# MCU.net
KiCad netlist of a schematic drawn in Altium Designer
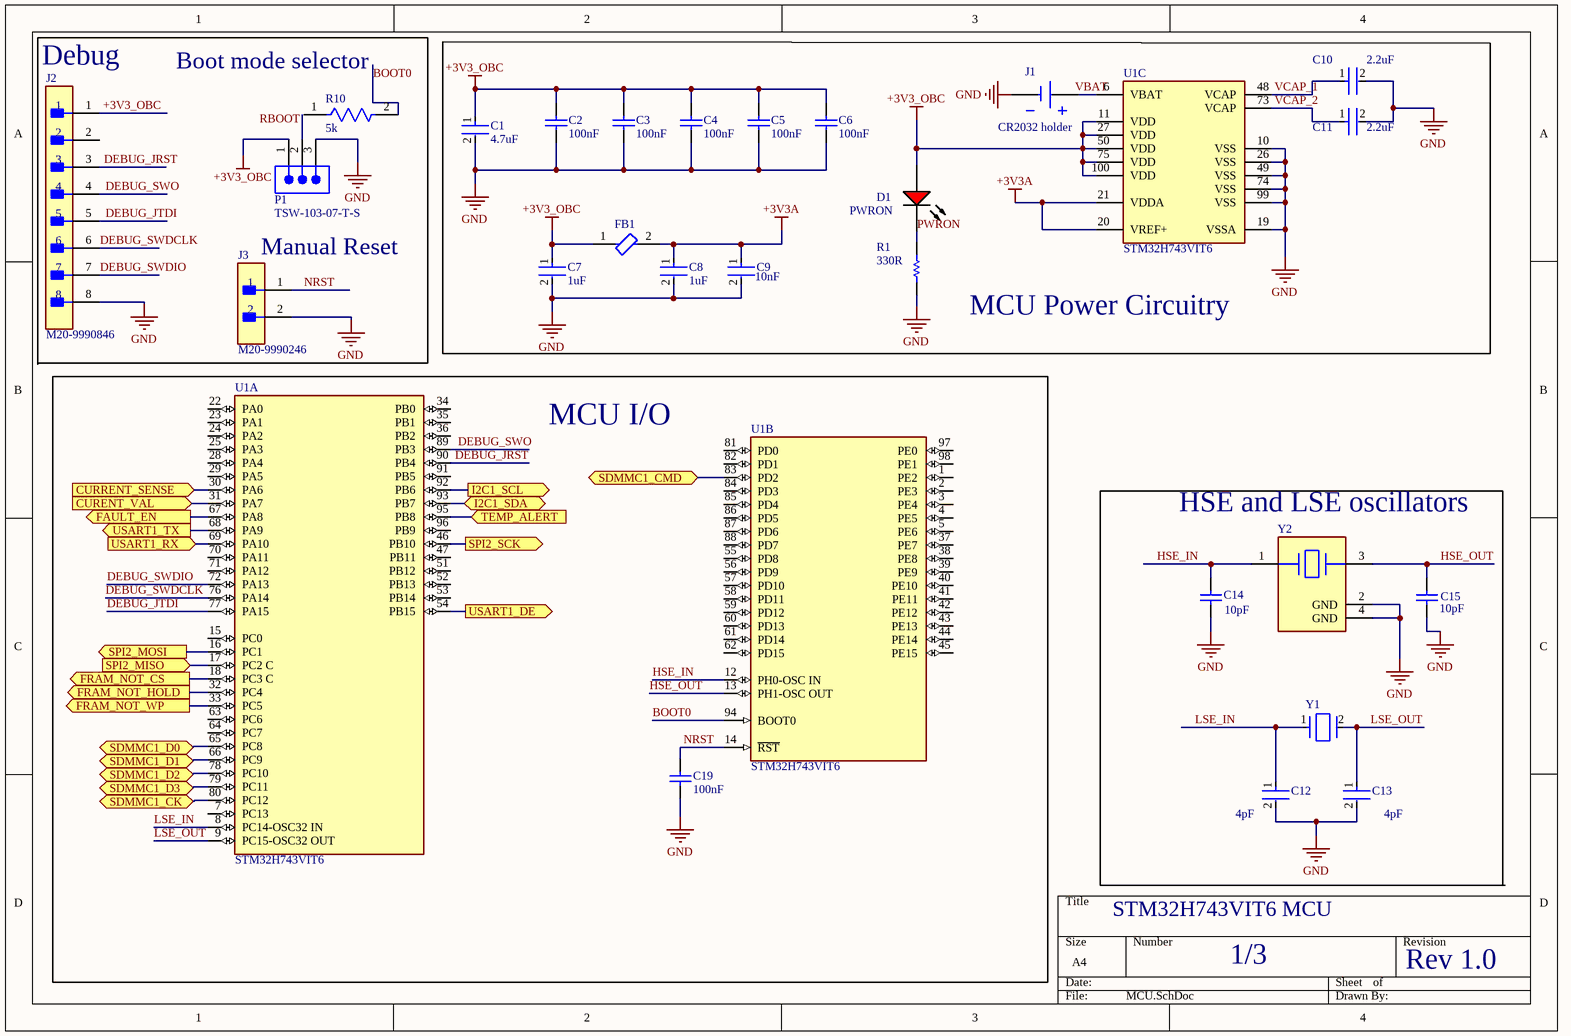
[diagram p0: MCU.SchDoc]

(export (version "E")
  (design (tool "Eeschema 10.0.6"))
  (components
    (comp (ref "C1")
      (value "4.7uF")
      (footprint "FP-0805-L_2_0_0_1-W_1_25-IPC_B")
      (description "Multilayer Ceramic Capacitor 4.7 uF 16V X7R 10% SMD 0805 T/R")
      (fields (field (name "TOLERANCE") "10%"))
      (libsource (lib "Altium Content Vault") (part "b4654b650e69147ec39a6b967a45e02"))
    )
    (comp (ref "C2")
      (value "100nF")
      (footprint "SAMS-C0603-2_M")
      (description "Multi-layer Ceramic Capacitor, -55 to 125 degC, 2-Pin SMD (0603), RoHS, Tape and Reel")
      (fields (field (name "MANUFACTURER") "Samsung Electro-Mechanics"))
      (libsource (lib "Altium Content Vault") (part "CAP-NP-2"))
    )
    (comp (ref "C3")
      (value "100nF")
      (footprint "SAMS-C0603-2_M")
      (description "Multi-layer Ceramic Capacitor, -55 to 125 degC, 2-Pin SMD (0603), RoHS, Tape and Reel")
      (fields (field (name "MANUFACTURER") "Samsung Electro-Mechanics"))
      (libsource (lib "Altium Content Vault") (part "CAP-NP-2"))
    )
    (comp (ref "C4")
      (value "100nF")
      (footprint "SAMS-C0603-2_M")
      (description "Multi-layer Ceramic Capacitor, -55 to 125 degC, 2-Pin SMD (0603), RoHS, Tape and Reel")
      (fields (field (name "MANUFACTURER") "Samsung Electro-Mechanics"))
      (libsource (lib "Altium Content Vault") (part "CAP-NP-2"))
    )
    (comp (ref "C5")
      (value "100nF")
      (footprint "SAMS-C0603-2_M")
      (description "Multi-layer Ceramic Capacitor, -55 to 125 degC, 2-Pin SMD (0603), RoHS, Tape and Reel")
      (fields (field (name "MANUFACTURER") "Samsung Electro-Mechanics"))
      (libsource (lib "Altium Content Vault") (part "CAP-NP-2"))
    )
    (comp (ref "C6")
      (value "100nF")
      (footprint "SAMS-C0603-2_M")
      (description "Multi-layer Ceramic Capacitor, -55 to 125 degC, 2-Pin SMD (0603), RoHS, Tape and Reel")
      (fields (field (name "MANUFACTURER") "Samsung Electro-Mechanics"))
      (libsource (lib "Altium Content Vault") (part "CAP-NP-2"))
    )
    (comp (ref "C7")
      (value "1uF")
      (footprint "FP-CL10-IPC_C")
      (description "Cap Ceramic 1uF 25V X5R ±10% Pad SMD 0603 +85°C T/R")
      (fields (field (name "VOLTAGE") "25V") (field (name "TOLERANCE") "10%"))
      (libsource (lib "Altium Content Vault") (part "b4654b650e69147ec39a6b967a45e02"))
    )
    (comp (ref "C8")
      (value "1uF")
      (footprint "FP-CL10-IPC_C")
      (description "Cap Ceramic 1uF 25V X5R ±10% Pad SMD 0603 +85°C T/R")
      (fields (field (name "VOLTAGE") "25V") (field (name "TOLERANCE") "10%"))
      (libsource (lib "Altium Content Vault") (part "b4654b650e69147ec39a6b967a45e02"))
    )
    (comp (ref "C9")
      (value "10nF")
      (footprint "FP-CC0402-MFG")
      (description "CAP CER 10000PF 10V X7R 0402")
      (fields
        (field (name "MANUFACTURER") "YAGEO")
        (field (name "MANUFACTURER PART NUMBER") "CC0402KRX7R6BB103")
      )
      (libsource (lib "Altium Content Vault") (part "11868f565c42a9108669ba33697ecf6"))
    )
    (comp (ref "C10")
      (value "2.2uF")
      (footprint "FP-CC0805-0_85-MFG")
      (description "CAP CER 2.2UF 25V X7R 0805")
      (fields
        (field (name "MANUFACTURER PART NUMBER") "CC0805KKX7R8BB225")
        (field (name "OCTOPART") "https://octopart.com/cc0805kkx7r8bb225-yageo-42522865")
      )
      (libsource (lib "Altium Content Vault") (part "11868f565c42a9108669ba33697ecf6"))
    )
    (comp (ref "C11")
      (value "2.2uF")
      (footprint "FP-CC0805-0_85-MFG")
      (description "CAP CER 2.2UF 25V X7R 0805")
      (fields
        (field (name "MANUFACTURER PART NUMBER") "CC0805KKX7R8BB225")
        (field (name "OCTOPART") "https://octopart.com/cc0805kkx7r8bb225-yageo-42522865")
      )
      (libsource (lib "Altium Content Vault") (part "11868f565c42a9108669ba33697ecf6"))
    )
    (comp (ref "C12")
      (value "4pF")
      (footprint "FP-GRM033-0_03-IPC_B")
      (description "Chip Multilayer Ceramic Capacitors for General Purpose, 0201, 4.0pF, C0G, 30ppm/°C, 0.25pF, 25V")
      (libsource (lib "Altium Content Vault") (part "b4654b650e69147ec39a6b967a45e02"))
    )
    (comp (ref "C13")
      (value "4pF")
      (footprint "FP-GRM033-0_03-IPC_B")
      (description "Chip Multilayer Ceramic Capacitors for General Purpose, 0201, 4.0pF, C0G, 30ppm/°C, 0.25pF, 25V")
      (libsource (lib "Altium Content Vault") (part "b4654b650e69147ec39a6b967a45e02"))
    )
    (comp (ref "C14")
      (value "10pF")
      (footprint "CAPC1005X55X25ML05T05")
      (description "Chip Capacitor, 10 pF, +/- 5%, 50 V, -55 to 125 degC, 0402 (1005 Metric), RoHS, Tape and Reel")
      (fields (field (name "TOLERANCE") "5%") (field (name "MANUFACTURER") "Yageo"))
      (libsource (lib "Altium Content Vault") (part "CAP-NP-2"))
    )
    (comp (ref "C15")
      (value "10pF")
      (footprint "CAPC1005X55X25ML05T05")
      (description "Chip Capacitor, 10 pF, +/- 5%, 50 V, -55 to 125 degC, 0402 (1005 Metric), RoHS, Tape and Reel")
      (fields (field (name "TOLERANCE") "5%") (field (name "MANUFACTURER") "Yageo"))
      (libsource (lib "Altium Content Vault") (part "CAP-NP-2"))
    )
    (comp (ref "C19")
      (value "100nF")
      (footprint "SAMS-C0603-2_M")
      (description "Multi-layer Ceramic Capacitor, -55 to 125 degC, 2-Pin SMD (0603), RoHS, Tape and Reel")
      (fields (field (name "MANUFACTURER") "Samsung Electro-Mechanics"))
      (libsource (lib "Altium Content Vault") (part "CAP-NP-2"))
    )
    (comp (ref "D1")
      (value "PWRON")
      (footprint "EVRL-0603-2_V")
      (description "Chip LED, Red, 5 V, 25 mA, -40 to 85 degC, 2-Pin SMD (0603), RoHS, Tape and Reel")
      (fields (field (name "MANUFACTURER") "Everlight Electronics"))
      (libsource (lib "Altium Content Vault") (part "LED-RED-AK-2"))
    )
    (comp (ref "FB1")
      (value "MMZ1005D121CTD25")
      (footprint "FP-MMZ1005-IPC_C")
      (description "Signal Line Ferrite Bead 120Ω @ 100MHz 350mA DCR 600mΩ AEC-Q200 SMD 0402")
      (libsource (lib "Altium Content Vault") (part "5f30dd21d616792df468990f7003faa"))
    )
    (comp (ref "J1")
      (value "CR2032 holder")
      (footprint "KEYSTONE-1025-7-2_V")
      (description "Holder for 2477 or 2430 Cells P/N 1025-7, Body 27.762 x 30.963 mm, THM")
      (fields (field (name "PARTNUMBER") "1025-7") (field (name "MANUFACTURER") "Keystone"))
      (libsource (lib "Altium Content Vault") (part "KEYSTONE-1025-7-2"))
    )
    (comp (ref "J2")
      (value "M20-9990846")
      (footprint "FP-M20-9990846-MFG")
      (description "CONN HEADER VERT 8POS 2.54MM")
      (libsource (lib "Altium Content Vault") (part "99ec2b232beb5d2356d4d77f6a047f0"))
    )
    (comp (ref "J3")
      (value "M20-9990246")
      (footprint "FP-M20-9990246-MFG")
      (description "CONN HEADER VERT 2POS 2.54MM")
      (fields
        (field (name "OCTOPART") "https://octopart.com/m20-9990246-harwin-2590635")
        (field (name "MANUFACTURER") "Harwin")
      )
      (libsource (lib "Altium Content Vault") (part "3bc925449376181038e59eaffc5286c"))
    )
    (comp (ref "P1")
      (value "TSW-103-07-T-S")
      (footprint "SMTC-TSW-103-07-X-S")
      (description "0.025\" SQ Post Header, Through-hole, Vertical, -55 to 105 degC, 2.54 mm Pitch, 3-Pin, Male, RoHS")
      (fields (field (name "MANUFACTURER") "Samtec"))
      (libsource (lib "Altium Content Vault") (part "SMTC-TSW-103-X-X-S-X"))
    )
    (comp (ref "R1")
      (value "330R")
      (footprint "RESC1608X55X25NL10T15")
      (description "Chip Resistor, 330 Ohm, +/- 1%, 0.1 W, -55 to 155 degC, 0603 (1608 Metric), RoHS, Tape and Reel")
      (fields (field (name "TOLERANCE") "10%"))
      (libsource (lib "Altium Content Vault") (part "RES-2"))
    )
    (comp (ref "R10")
      (value "5k")
      (footprint "FP-MCR01-MFG")
      (description "Thick Film Chip Resistor, 0402, 5.1kΩ, 1%, 100ppm/°C, 0.063W, 50V")
      (fields (field (name "TOLERANCE") "1%"))
      (libsource (lib "Altium Content Vault") (part "1029c3af85768c4190bb7ad29bc67b5"))
    )
    (comp (ref "U1")
      (value "STM32H743VIT6")
      (footprint "FP-LQFP100-1L-MFG")
      (description "IC MCU 32BIT 2MB FLASH 100LQFP")
      (fields
        (field (name "OCTOPART") "https://octopart.com/stm32h743vit6-stmicroelectronics-76372527")
        (field (name "MANUFACTURER") "STMicroelectronics")
      )
      (libsource (lib "Altium Content Vault") (part "01082ce2885d1d16a22823c45526fe6"))
    )
    (comp (ref "Y1")
      (value "ABS06-107-32.768KHZ-T")
      (footprint "FP-ABS06-MFG")
      (description "CRYSTAL 32.7680KHZ 4PF SMD")
      (fields (field (name "TOLERANCE") "20ppm"))
      (libsource (lib "Altium Content Vault") (part "c23a69dc6c9e2f18f2079038eb95dd1"))
    )
    (comp (ref "Y2")
      (value "ABM3B-25.000MHZ-10-1-U-T")
      (footprint "FP-ABM3B-MFG")
      (description "Crystal 25MHz ±10ppm 10pF SMD-4 5mm x 3.2mm")
      (fields (field (name "TOLERANCE") "10ppm"))
      (libsource (lib "Altium Content Vault") (part "48e526d86b7f2615d98721063c72f49"))
    )
  )
  (nets
    (net (code "1") (name "+3V3A") (class "Default")
      (node (ref "C8") (pin "1") (pinfunction "1_1") (pintype "passive"))
      (node (ref "C9") (pin "1") (pinfunction "1_1") (pintype "passive"))
      (node (ref "FB1") (pin "2") (pinfunction "2_2") (pintype "passive"))
      (node (ref "U1") (pin "20") (pinfunction "VREF+_20") (pintype "power_in"))
      (node (ref "U1") (pin "21") (pinfunction "VDDA_21") (pintype "power_in"))
    )
    (net (code "2") (name "+3V3_OBC") (class "Default")
      (node (ref "C1") (pin "1") (pinfunction "1_1") (pintype "passive"))
      (node (ref "C2") (pin "2") (pinfunction "2_2") (pintype "passive"))
      (node (ref "C3") (pin "2") (pinfunction "2_2") (pintype "passive"))
      (node (ref "C4") (pin "2") (pinfunction "2_2") (pintype "passive"))
      (node (ref "C5") (pin "2") (pinfunction "2_2") (pintype "passive"))
      (node (ref "C6") (pin "2") (pinfunction "2_2") (pintype "passive"))
      (node (ref "C7") (pin "1") (pinfunction "1_1") (pintype "passive"))
      (node (ref "D1") (pin "1") (pinfunction "A_1") (pintype "passive"))
      (node (ref "FB1") (pin "1") (pinfunction "1_1") (pintype "passive"))
      (node (ref "J2") (pin "1") (pinfunction "1_1") (pintype "passive"))
      (node (ref "P1") (pin "1") (pinfunction "1_1") (pintype "passive"))
      (node (ref "U1") (pin "100") (pinfunction "VDD_100") (pintype "power_in"))
      (node (ref "U1") (pin "11") (pinfunction "VDD_11") (pintype "power_in"))
      (node (ref "U1") (pin "27") (pinfunction "VDD_27") (pintype "power_in"))
      (node (ref "U1") (pin "50") (pinfunction "VDD_50") (pintype "power_in"))
      (node (ref "U1") (pin "75") (pinfunction "VDD_75") (pintype "power_in"))
    )
    (net (code "3") (name "/BOOT0") (class "Default")
      (node (ref "R10") (pin "2") (pinfunction "2_2") (pintype "passive"))
      (node (ref "U1") (pin "94") (pinfunction "BOOT0_94") (pintype "input"))
    )
    (net (code "4") (name "/CURENT_VAL") (class "Default")
      (node (ref "U1") (pin "31") (pinfunction "PA7_31") (pintype "bidirectional"))
    )
    (net (code "5") (name "/CURRENT_SENSE") (class "Default")
      (node (ref "U1") (pin "30") (pinfunction "PA6_30") (pintype "bidirectional"))
    )
    (net (code "6") (name "/DEBUG_JRST") (class "Default")
      (node (ref "J2") (pin "3") (pinfunction "3_3") (pintype "passive"))
      (node (ref "U1") (pin "90") (pinfunction "PB4_90") (pintype "bidirectional"))
    )
    (net (code "7") (name "/DEBUG_JTDI") (class "Default")
      (node (ref "J2") (pin "5") (pinfunction "5_5") (pintype "passive"))
      (node (ref "U1") (pin "77") (pinfunction "PA15_77") (pintype "bidirectional"))
    )
    (net (code "8") (name "/DEBUG_SWDCLK") (class "Default")
      (node (ref "J2") (pin "6") (pinfunction "6_6") (pintype "passive"))
      (node (ref "U1") (pin "76") (pinfunction "PA14_76") (pintype "bidirectional"))
    )
    (net (code "9") (name "/DEBUG_SWDIO") (class "Default")
      (node (ref "J2") (pin "7") (pinfunction "7_7") (pintype "passive"))
      (node (ref "U1") (pin "72") (pinfunction "PA13_72") (pintype "bidirectional"))
    )
    (net (code "10") (name "/DEBUG_SWO") (class "Default")
      (node (ref "J2") (pin "4") (pinfunction "4_4") (pintype "passive"))
      (node (ref "U1") (pin "89") (pinfunction "PB3_89") (pintype "bidirectional"))
    )
    (net (code "11") (name "/FAULT_EN") (class "Default")
      (node (ref "U1") (pin "67") (pinfunction "PA8_67") (pintype "bidirectional"))
    )
    (net (code "12") (name "/FRAM_NOT_CS") (class "Default")
      (node (ref "U1") (pin "18") (pinfunction "PC3_C_18") (pintype "bidirectional"))
    )
    (net (code "13") (name "/FRAM_NOT_HOLD") (class "Default")
      (node (ref "U1") (pin "32") (pinfunction "PC4_32") (pintype "bidirectional"))
    )
    (net (code "14") (name "/FRAM_NOT_WP") (class "Default")
      (node (ref "U1") (pin "33") (pinfunction "PC5_33") (pintype "bidirectional"))
    )
    (net (code "15") (name "/HSE_IN") (class "Default")
      (node (ref "C14") (pin "2") (pinfunction "2_2") (pintype "passive"))
      (node (ref "U1") (pin "12") (pinfunction "PH0-OSC_IN_12") (pintype "bidirectional"))
      (node (ref "Y2") (pin "1") (pinfunction "1_1") (pintype "passive"))
    )
    (net (code "16") (name "/HSE_OUT") (class "Default")
      (node (ref "C15") (pin "2") (pinfunction "2_2") (pintype "passive"))
      (node (ref "U1") (pin "13") (pinfunction "PH1-OSC_OUT_13") (pintype "bidirectional"))
      (node (ref "Y2") (pin "3") (pinfunction "3_3") (pintype "passive"))
    )
    (net (code "17") (name "/I2C1_SCL") (class "Default")
      (node (ref "U1") (pin "92") (pinfunction "PB6_92") (pintype "bidirectional"))
    )
    (net (code "18") (name "/I2C1_SDA") (class "Default")
      (node (ref "U1") (pin "93") (pinfunction "PB7_93") (pintype "bidirectional"))
    )
    (net (code "19") (name "/LSE_IN") (class "Default")
      (node (ref "C12") (pin "1") (pinfunction "1_1") (pintype "passive"))
      (node (ref "U1") (pin "8") (pinfunction "PC14-OSC32_IN_8") (pintype "bidirectional"))
      (node (ref "Y1") (pin "1") (pinfunction "1_1") (pintype "passive"))
    )
    (net (code "20") (name "/LSE_OUT") (class "Default")
      (node (ref "C13") (pin "1") (pinfunction "1_1") (pintype "passive"))
      (node (ref "U1") (pin "9") (pinfunction "PC15-OSC32_OUT_9") (pintype "bidirectional"))
      (node (ref "Y1") (pin "2") (pinfunction "2_2") (pintype "passive"))
    )
    (net (code "21") (name "/NRST") (class "Default")
      (node (ref "C19") (pin "2") (pinfunction "2_2") (pintype "passive"))
      (node (ref "J3") (pin "1") (pinfunction "1_1") (pintype "passive"))
      (node (ref "U1") (pin "14") (pinfunction "~{RST}_14") (pintype "input"))
    )
    (net (code "22") (name "/PWRON") (class "Default")
      (node (ref "D1") (pin "2") (pinfunction "K_2") (pintype "passive"))
      (node (ref "R1") (pin "2") (pinfunction "2_2") (pintype "passive"))
    )
    (net (code "24") (name "/SDMMC1_CK") (class "Default")
      (node (ref "U1") (pin "80") (pinfunction "PC12_80") (pintype "bidirectional"))
    )
    (net (code "25") (name "/SDMMC1_CMD") (class "Default")
      (node (ref "U1") (pin "83") (pinfunction "PD2_83") (pintype "bidirectional"))
    )
    (net (code "26") (name "/SDMMC1_D0") (class "Default")
      (node (ref "U1") (pin "65") (pinfunction "PC8_65") (pintype "bidirectional"))
    )
    (net (code "27") (name "/SDMMC1_D1") (class "Default")
      (node (ref "U1") (pin "66") (pinfunction "PC9_66") (pintype "bidirectional"))
    )
    (net (code "28") (name "/SDMMC1_D2") (class "Default")
      (node (ref "U1") (pin "78") (pinfunction "PC10_78") (pintype "bidirectional"))
    )
    (net (code "29") (name "/SDMMC1_D3") (class "Default")
      (node (ref "U1") (pin "79") (pinfunction "PC11_79") (pintype "bidirectional"))
    )
    (net (code "30") (name "/SPI2_MISO") (class "Default")
      (node (ref "U1") (pin "17") (pinfunction "PC2_C_17") (pintype "bidirectional"))
    )
    (net (code "31") (name "/SPI2_MOSI") (class "Default")
      (node (ref "U1") (pin "16") (pinfunction "PC1_16") (pintype "bidirectional"))
    )
    (net (code "32") (name "/SPI2_SCK") (class "Default")
      (node (ref "U1") (pin "46") (pinfunction "PB10_46") (pintype "bidirectional"))
    )
    (net (code "33") (name "/TEMP_ALERT") (class "Default")
      (node (ref "U1") (pin "95") (pinfunction "PB8_95") (pintype "bidirectional"))
    )
    (net (code "34") (name "/USART1_DE") (class "Default")
      (node (ref "U1") (pin "54") (pinfunction "PB15_54") (pintype "bidirectional"))
    )
    (net (code "35") (name "/USART1_RX") (class "Default")
      (node (ref "U1") (pin "69") (pinfunction "PA10_69") (pintype "bidirectional"))
    )
    (net (code "36") (name "/USART1_TX") (class "Default")
      (node (ref "U1") (pin "68") (pinfunction "PA9_68") (pintype "bidirectional"))
    )
    (net (code "38") (name "/VCAP_1") (class "Default")
      (node (ref "C10") (pin "1") (pinfunction "1_1") (pintype "passive"))
      (node (ref "U1") (pin "48") (pinfunction "VCAP_48") (pintype "passive"))
    )
    (net (code "39") (name "/VCAP_2") (class "Default")
      (node (ref "C11") (pin "1") (pinfunction "1_1") (pintype "passive"))
      (node (ref "U1") (pin "73") (pinfunction "VCAP_73") (pintype "passive"))
    )
    (net (code "40") (name "GND") (class "Default")
      (node (ref "C1") (pin "2") (pinfunction "2_2") (pintype "passive"))
      (node (ref "C10") (pin "2") (pinfunction "2_2") (pintype "passive"))
      (node (ref "C11") (pin "2") (pinfunction "2_2") (pintype "passive"))
      (node (ref "C12") (pin "2") (pinfunction "2_2") (pintype "passive"))
      (node (ref "C13") (pin "2") (pinfunction "2_2") (pintype "passive"))
      (node (ref "C14") (pin "1") (pinfunction "1_1") (pintype "passive"))
      (node (ref "C15") (pin "1") (pinfunction "1_1") (pintype "passive"))
      (node (ref "C19") (pin "1") (pinfunction "1_1") (pintype "passive"))
      (node (ref "C2") (pin "1") (pinfunction "1_1") (pintype "passive"))
      (node (ref "C3") (pin "1") (pinfunction "1_1") (pintype "passive"))
      (node (ref "C4") (pin "1") (pinfunction "1_1") (pintype "passive"))
      (node (ref "C5") (pin "1") (pinfunction "1_1") (pintype "passive"))
      (node (ref "C6") (pin "1") (pinfunction "1_1") (pintype "passive"))
      (node (ref "C7") (pin "2") (pinfunction "2_2") (pintype "passive"))
      (node (ref "C8") (pin "2") (pinfunction "2_2") (pintype "passive"))
      (node (ref "C9") (pin "2") (pinfunction "2_2") (pintype "passive"))
      (node (ref "J1") (pin "2") (pinfunction "-_2") (pintype "passive"))
      (node (ref "J2") (pin "8") (pinfunction "8_8") (pintype "passive"))
      (node (ref "J3") (pin "2") (pinfunction "2_2") (pintype "passive"))
      (node (ref "P1") (pin "3") (pinfunction "3_3") (pintype "passive"))
      (node (ref "R1") (pin "1") (pinfunction "1_1") (pintype "passive"))
      (node (ref "U1") (pin "10") (pinfunction "VSS_10") (pintype "power_in"))
      (node (ref "U1") (pin "19") (pinfunction "VSSA_19") (pintype "power_in"))
      (node (ref "U1") (pin "26") (pinfunction "VSS_26") (pintype "power_in"))
      (node (ref "U1") (pin "49") (pinfunction "VSS_49") (pintype "power_in"))
      (node (ref "U1") (pin "74") (pinfunction "VSS_74") (pintype "power_in"))
      (node (ref "U1") (pin "99") (pinfunction "VSS_99") (pintype "power_in"))
      (node (ref "Y2") (pin "2") (pinfunction "GND_2") (pintype "power_in"))
      (node (ref "Y2") (pin "4") (pinfunction "GND_4") (pintype "power_in"))
    )
    (net (code "41") (name "Net-(J1-+)") (class "Default")
      (node (ref "J1") (pin "1") (pinfunction "+_1") (pintype "passive"))
      (node (ref "U1") (pin "6") (pinfunction "VBAT_6") (pintype "power_in"))
    )
    (net (code "42") (name "unconnected-(J2-Pad2)") (class "Default")
      (node (ref "J2") (pin "2") (pinfunction "2_2") (pintype "passive"))
    )
    (net (code "43") (name "unconnected-(P1-Pad2)") (class "Default")
      (node (ref "P1") (pin "2") (pinfunction "2_2") (pintype "passive"))
    )
    (net (code "44") (name "unconnected-(R10-Pad1)") (class "Default")
      (node (ref "R10") (pin "1") (pinfunction "1_1") (pintype "passive"))
    )
    (net (code "45") (name "unconnected-(U1A-PA0-Pad22)") (class "Default")
      (node (ref "U1") (pin "22") (pinfunction "PA0_22") (pintype "bidirectional"))
    )
    (net (code "46") (name "unconnected-(U1A-PA1-Pad23)") (class "Default")
      (node (ref "U1") (pin "23") (pinfunction "PA1_23") (pintype "bidirectional"))
    )
    (net (code "47") (name "unconnected-(U1A-PA2-Pad24)") (class "Default")
      (node (ref "U1") (pin "24") (pinfunction "PA2_24") (pintype "bidirectional"))
    )
    (net (code "48") (name "unconnected-(U1A-PA3-Pad25)") (class "Default")
      (node (ref "U1") (pin "25") (pinfunction "PA3_25") (pintype "bidirectional"))
    )
    (net (code "49") (name "unconnected-(U1A-PA4-Pad28)") (class "Default")
      (node (ref "U1") (pin "28") (pinfunction "PA4_28") (pintype "bidirectional"))
    )
    (net (code "50") (name "unconnected-(U1A-PA5-Pad29)") (class "Default")
      (node (ref "U1") (pin "29") (pinfunction "PA5_29") (pintype "bidirectional"))
    )
    (net (code "51") (name "unconnected-(U1A-PA11-Pad70)") (class "Default")
      (node (ref "U1") (pin "70") (pinfunction "PA11_70") (pintype "bidirectional"))
    )
    (net (code "52") (name "unconnected-(U1A-PA12-Pad71)") (class "Default")
      (node (ref "U1") (pin "71") (pinfunction "PA12_71") (pintype "bidirectional"))
    )
    (net (code "53") (name "unconnected-(U1A-PB0-Pad34)") (class "Default")
      (node (ref "U1") (pin "34") (pinfunction "PB0_34") (pintype "bidirectional"))
    )
    (net (code "54") (name "unconnected-(U1A-PB1-Pad35)") (class "Default")
      (node (ref "U1") (pin "35") (pinfunction "PB1_35") (pintype "bidirectional"))
    )
    (net (code "55") (name "unconnected-(U1A-PB2-Pad36)") (class "Default")
      (node (ref "U1") (pin "36") (pinfunction "PB2_36") (pintype "bidirectional"))
    )
    (net (code "56") (name "unconnected-(U1A-PB5-Pad91)") (class "Default")
      (node (ref "U1") (pin "91") (pinfunction "PB5_91") (pintype "bidirectional"))
    )
    (net (code "57") (name "unconnected-(U1A-PB9-Pad96)") (class "Default")
      (node (ref "U1") (pin "96") (pinfunction "PB9_96") (pintype "bidirectional"))
    )
    (net (code "58") (name "unconnected-(U1A-PB11-Pad47)") (class "Default")
      (node (ref "U1") (pin "47") (pinfunction "PB11_47") (pintype "bidirectional"))
    )
    (net (code "59") (name "unconnected-(U1A-PB12-Pad51)") (class "Default")
      (node (ref "U1") (pin "51") (pinfunction "PB12_51") (pintype "bidirectional"))
    )
    (net (code "60") (name "unconnected-(U1A-PB13-Pad52)") (class "Default")
      (node (ref "U1") (pin "52") (pinfunction "PB13_52") (pintype "bidirectional"))
    )
    (net (code "61") (name "unconnected-(U1A-PB14-Pad53)") (class "Default")
      (node (ref "U1") (pin "53") (pinfunction "PB14_53") (pintype "bidirectional"))
    )
    (net (code "62") (name "unconnected-(U1A-PC0-Pad15)") (class "Default")
      (node (ref "U1") (pin "15") (pinfunction "PC0_15") (pintype "bidirectional"))
    )
    (net (code "63") (name "unconnected-(U1A-PC6-Pad63)") (class "Default")
      (node (ref "U1") (pin "63") (pinfunction "PC6_63") (pintype "bidirectional"))
    )
    (net (code "64") (name "unconnected-(U1A-PC7-Pad64)") (class "Default")
      (node (ref "U1") (pin "64") (pinfunction "PC7_64") (pintype "bidirectional"))
    )
    (net (code "65") (name "unconnected-(U1A-PC13-Pad7)") (class "Default")
      (node (ref "U1") (pin "7") (pinfunction "PC13_7") (pintype "bidirectional"))
    )
    (net (code "66") (name "unconnected-(U1B-PD0-Pad81)") (class "Default")
      (node (ref "U1") (pin "81") (pinfunction "PD0_81") (pintype "bidirectional"))
    )
    (net (code "67") (name "unconnected-(U1B-PD1-Pad82)") (class "Default")
      (node (ref "U1") (pin "82") (pinfunction "PD1_82") (pintype "bidirectional"))
    )
    (net (code "68") (name "unconnected-(U1B-PD3-Pad84)") (class "Default")
      (node (ref "U1") (pin "84") (pinfunction "PD3_84") (pintype "bidirectional"))
    )
    (net (code "69") (name "unconnected-(U1B-PD4-Pad85)") (class "Default")
      (node (ref "U1") (pin "85") (pinfunction "PD4_85") (pintype "bidirectional"))
    )
    (net (code "70") (name "unconnected-(U1B-PD5-Pad86)") (class "Default")
      (node (ref "U1") (pin "86") (pinfunction "PD5_86") (pintype "bidirectional"))
    )
    (net (code "71") (name "unconnected-(U1B-PD6-Pad87)") (class "Default")
      (node (ref "U1") (pin "87") (pinfunction "PD6_87") (pintype "bidirectional"))
    )
    (net (code "72") (name "unconnected-(U1B-PD7-Pad88)") (class "Default")
      (node (ref "U1") (pin "88") (pinfunction "PD7_88") (pintype "bidirectional"))
    )
    (net (code "73") (name "unconnected-(U1B-PD8-Pad55)") (class "Default")
      (node (ref "U1") (pin "55") (pinfunction "PD8_55") (pintype "bidirectional"))
    )
    (net (code "74") (name "unconnected-(U1B-PD9-Pad56)") (class "Default")
      (node (ref "U1") (pin "56") (pinfunction "PD9_56") (pintype "bidirectional"))
    )
    (net (code "75") (name "unconnected-(U1B-PD10-Pad57)") (class "Default")
      (node (ref "U1") (pin "57") (pinfunction "PD10_57") (pintype "bidirectional"))
    )
    (net (code "76") (name "unconnected-(U1B-PD11-Pad58)") (class "Default")
      (node (ref "U1") (pin "58") (pinfunction "PD11_58") (pintype "bidirectional"))
    )
    (net (code "77") (name "unconnected-(U1B-PD12-Pad59)") (class "Default")
      (node (ref "U1") (pin "59") (pinfunction "PD12_59") (pintype "bidirectional"))
    )
    (net (code "78") (name "unconnected-(U1B-PD13-Pad60)") (class "Default")
      (node (ref "U1") (pin "60") (pinfunction "PD13_60") (pintype "bidirectional"))
    )
    (net (code "79") (name "unconnected-(U1B-PD14-Pad61)") (class "Default")
      (node (ref "U1") (pin "61") (pinfunction "PD14_61") (pintype "bidirectional"))
    )
    (net (code "80") (name "unconnected-(U1B-PD15-Pad62)") (class "Default")
      (node (ref "U1") (pin "62") (pinfunction "PD15_62") (pintype "bidirectional"))
    )
    (net (code "81") (name "unconnected-(U1B-PE0-Pad97)") (class "Default")
      (node (ref "U1") (pin "97") (pinfunction "PE0_97") (pintype "bidirectional"))
    )
    (net (code "82") (name "unconnected-(U1B-PE1-Pad98)") (class "Default")
      (node (ref "U1") (pin "98") (pinfunction "PE1_98") (pintype "bidirectional"))
    )
    (net (code "83") (name "unconnected-(U1B-PE2-Pad1)") (class "Default")
      (node (ref "U1") (pin "1") (pinfunction "PE2_1") (pintype "bidirectional"))
    )
    (net (code "84") (name "unconnected-(U1B-PE3-Pad2)") (class "Default")
      (node (ref "U1") (pin "2") (pinfunction "PE3_2") (pintype "bidirectional"))
    )
    (net (code "85") (name "unconnected-(U1B-PE4-Pad3)") (class "Default")
      (node (ref "U1") (pin "3") (pinfunction "PE4_3") (pintype "bidirectional"))
    )
    (net (code "86") (name "unconnected-(U1B-PE5-Pad4)") (class "Default")
      (node (ref "U1") (pin "4") (pinfunction "PE5_4") (pintype "bidirectional"))
    )
    (net (code "87") (name "unconnected-(U1B-PE6-Pad5)") (class "Default")
      (node (ref "U1") (pin "5") (pinfunction "PE6_5") (pintype "bidirectional"))
    )
    (net (code "88") (name "unconnected-(U1B-PE7-Pad37)") (class "Default")
      (node (ref "U1") (pin "37") (pinfunction "PE7_37") (pintype "bidirectional"))
    )
    (net (code "89") (name "unconnected-(U1B-PE8-Pad38)") (class "Default")
      (node (ref "U1") (pin "38") (pinfunction "PE8_38") (pintype "bidirectional"))
    )
    (net (code "90") (name "unconnected-(U1B-PE9-Pad39)") (class "Default")
      (node (ref "U1") (pin "39") (pinfunction "PE9_39") (pintype "bidirectional"))
    )
    (net (code "91") (name "unconnected-(U1B-PE10-Pad40)") (class "Default")
      (node (ref "U1") (pin "40") (pinfunction "PE10_40") (pintype "bidirectional"))
    )
    (net (code "92") (name "unconnected-(U1B-PE11-Pad41)") (class "Default")
      (node (ref "U1") (pin "41") (pinfunction "PE11_41") (pintype "bidirectional"))
    )
    (net (code "93") (name "unconnected-(U1B-PE12-Pad42)") (class "Default")
      (node (ref "U1") (pin "42") (pinfunction "PE12_42") (pintype "bidirectional"))
    )
    (net (code "94") (name "unconnected-(U1B-PE13-Pad43)") (class "Default")
      (node (ref "U1") (pin "43") (pinfunction "PE13_43") (pintype "bidirectional"))
    )
    (net (code "95") (name "unconnected-(U1B-PE14-Pad44)") (class "Default")
      (node (ref "U1") (pin "44") (pinfunction "PE14_44") (pintype "bidirectional"))
    )
    (net (code "96") (name "unconnected-(U1B-PE15-Pad45)") (class "Default")
      (node (ref "U1") (pin "45") (pinfunction "PE15_45") (pintype "bidirectional"))
    )
  )
)
